# atmega128rf.net
KiCad netlist of a schematic drawn in Altium Designer
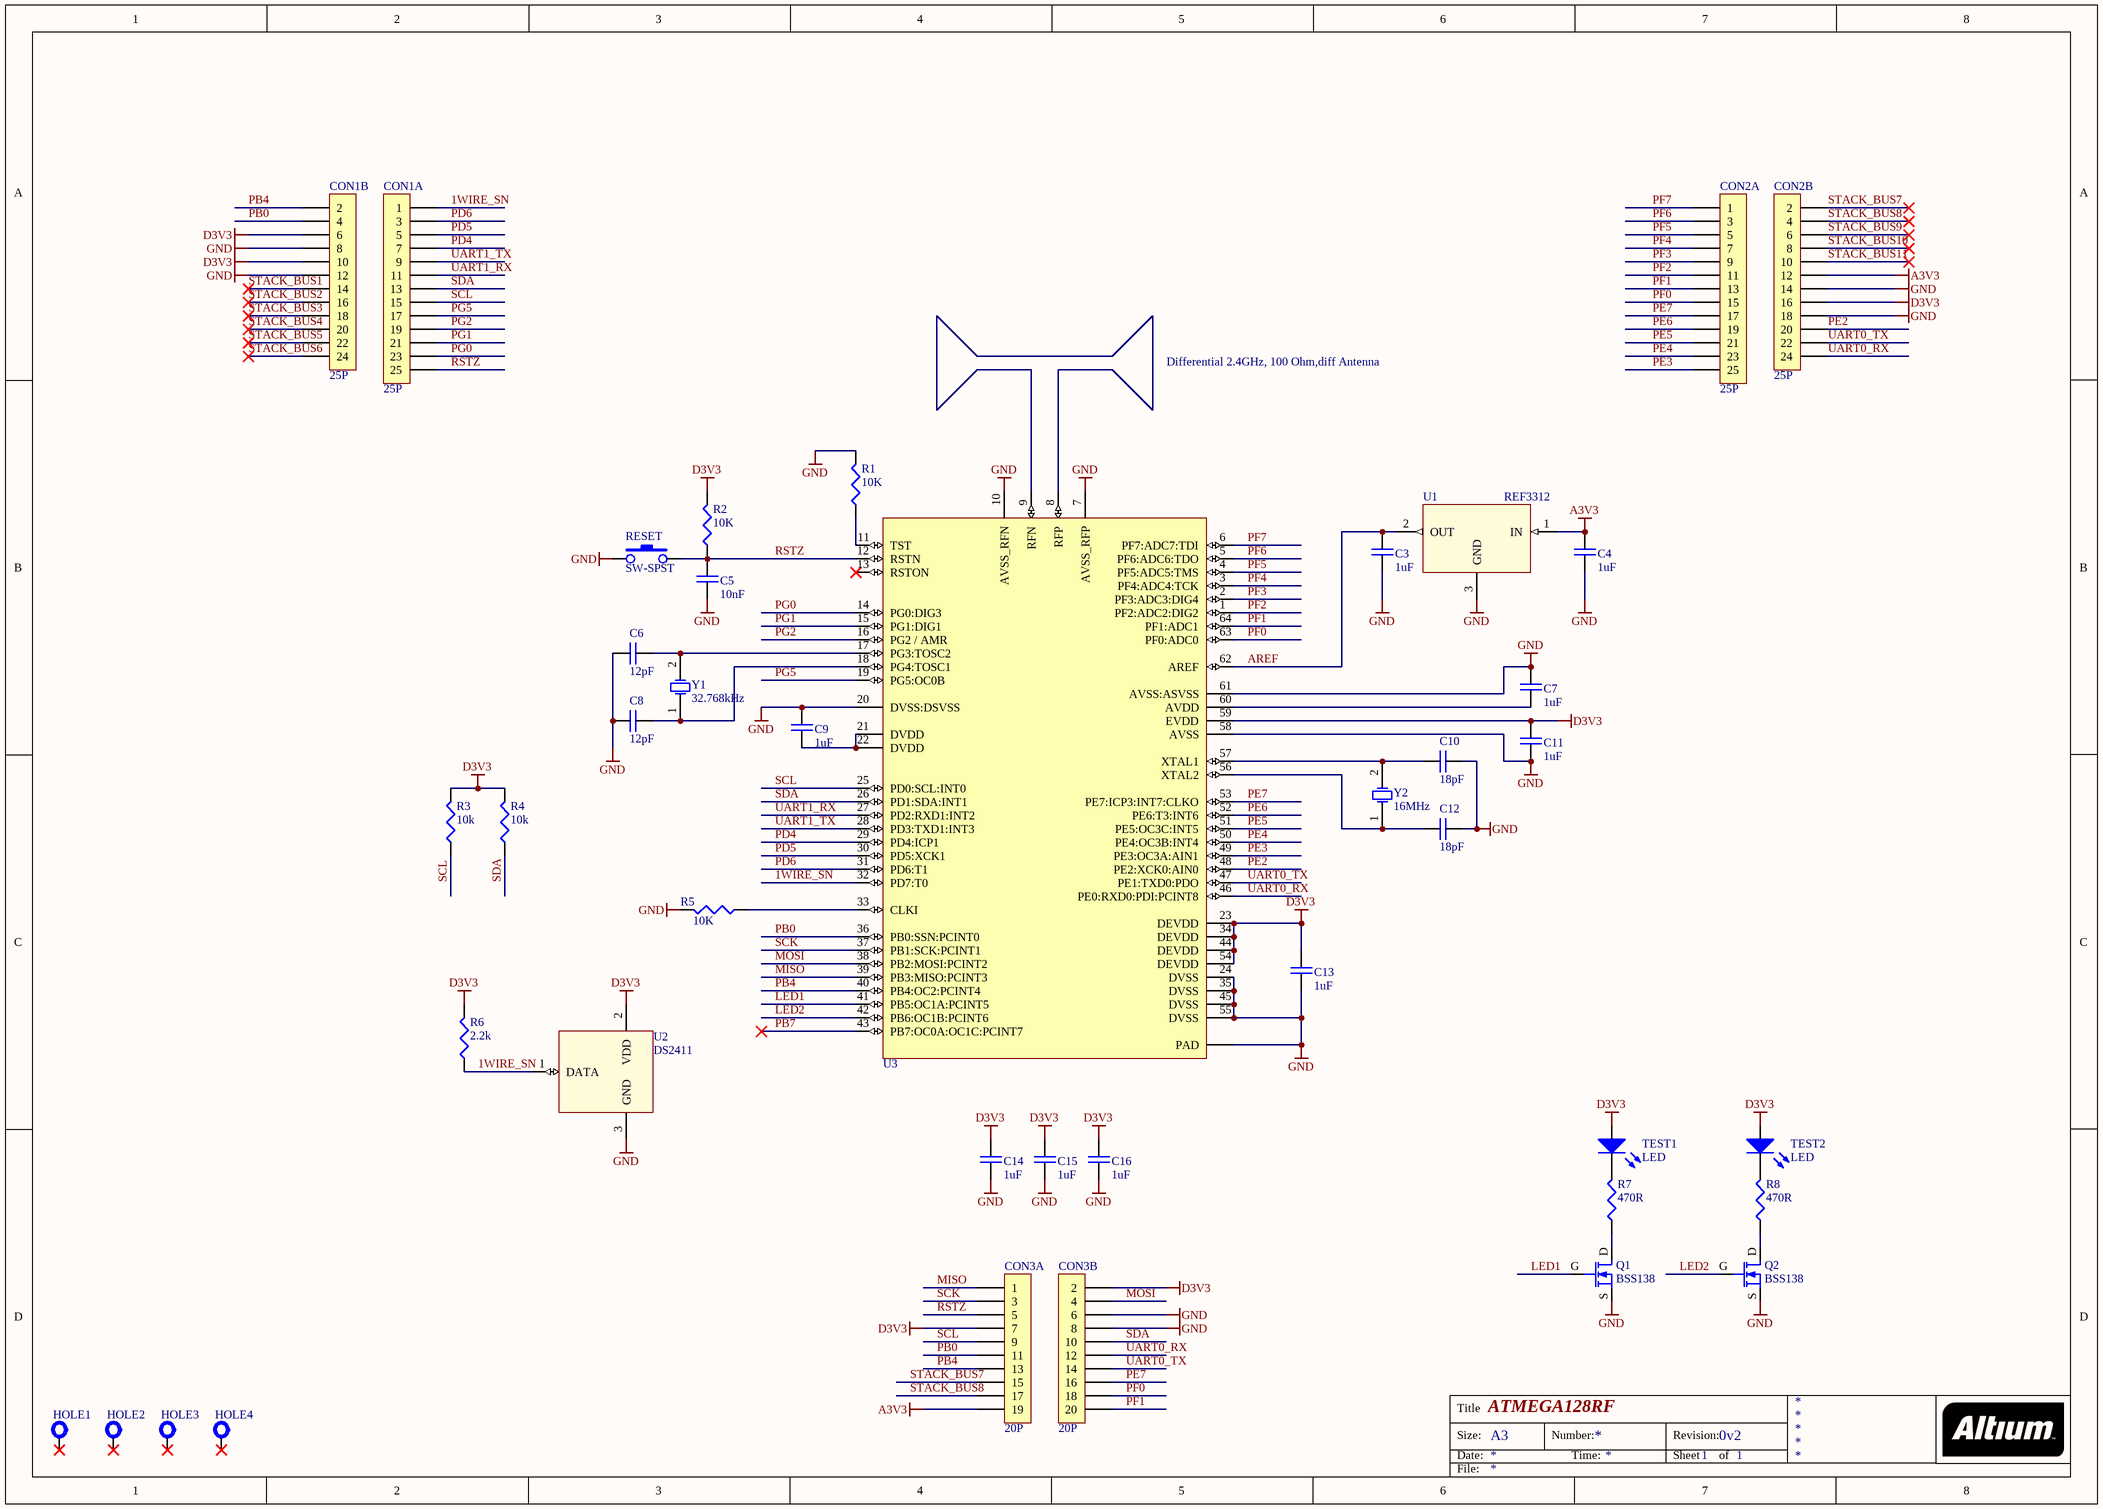
[diagram p0: atmega128rf.SchDoc]

(export (version "E")
  (design (tool "Eeschema 10.0.6"))
  (components
    (comp (ref "C3")
      (value "1uF")
      (footprint "0603")
      (description "Capacitor")
      (fields (field (name "OWNER") "Nuno Brum"))
      (libsource (lib "Alcetronics_Devices") (part "CAP"))
    )
    (comp (ref "C4")
      (value "1uF")
      (footprint "0603")
      (description "Capacitor")
      (fields (field (name "OWNER") "Nuno Brum"))
      (libsource (lib "Alcetronics_Devices") (part "CAP"))
    )
    (comp (ref "C5")
      (value "10nF")
      (footprint "0603")
      (description "Capacitor")
      (fields (field (name "OWNER") "Nuno Brum"))
      (libsource (lib "Alcetronics_Devices") (part "CAP"))
    )
    (comp (ref "C6")
      (value "12pF")
      (footprint "0603")
      (description "Capacitor")
      (fields (field (name "OWNER") "Nuno Brum"))
      (libsource (lib "Alcetronics_Devices") (part "CAP"))
    )
    (comp (ref "C7")
      (value "1uF")
      (footprint "0603")
      (description "Capacitor")
      (fields (field (name "OWNER") "Nuno Brum"))
      (libsource (lib "Alcetronics_Devices") (part "CAP"))
    )
    (comp (ref "C8")
      (value "12pF")
      (footprint "0603")
      (description "Capacitor")
      (fields (field (name "OWNER") "Nuno Brum"))
      (libsource (lib "Alcetronics_Devices") (part "CAP"))
    )
    (comp (ref "C9")
      (value "1uF")
      (footprint "0603")
      (description "Capacitor")
      (fields (field (name "OWNER") "Nuno Brum"))
      (libsource (lib "Alcetronics_Devices") (part "CAP"))
    )
    (comp (ref "C10")
      (value "18pF")
      (footprint "0603")
      (description "Capacitor")
      (fields (field (name "OWNER") "Nuno Brum"))
      (libsource (lib "Alcetronics_Devices") (part "CAP"))
    )
    (comp (ref "C11")
      (value "1uF")
      (footprint "0603")
      (description "Capacitor")
      (fields (field (name "OWNER") "Nuno Brum"))
      (libsource (lib "Alcetronics_Devices") (part "CAP"))
    )
    (comp (ref "C12")
      (value "18pF")
      (footprint "0603")
      (description "Capacitor")
      (fields (field (name "OWNER") "Nuno Brum"))
      (libsource (lib "Alcetronics_Devices") (part "CAP"))
    )
    (comp (ref "C13")
      (value "1uF")
      (footprint "0603")
      (description "Capacitor")
      (fields (field (name "OWNER") "Nuno Brum"))
      (libsource (lib "Alcetronics_Devices") (part "CAP"))
    )
    (comp (ref "C14")
      (value "1uF")
      (footprint "0603")
      (description "Capacitor")
      (fields (field (name "OWNER") "Nuno Brum"))
      (libsource (lib "Alcetronics_Devices") (part "CAP"))
    )
    (comp (ref "C15")
      (value "1uF")
      (footprint "0603")
      (description "Capacitor")
      (fields (field (name "OWNER") "Nuno Brum"))
      (libsource (lib "Alcetronics_Devices") (part "CAP"))
    )
    (comp (ref "C16")
      (value "1uF")
      (footprint "0603")
      (description "Capacitor")
      (fields (field (name "OWNER") "Nuno Brum"))
      (libsource (lib "Alcetronics_Devices") (part "CAP"))
    )
    (comp (ref "CON1")
      (value "25P")
      (footprint "DF9-25-STACK")
      (description "Connector 25 Pins")
      (fields (field (name "OWNER") "Ricardo Rodrigues"))
      (libsource (lib "Alcetronics_EM") (part "CON25"))
    )
    (comp (ref "CON2")
      (value "25P")
      (footprint "DF9-25-STACK")
      (description "Connector 25 Pins")
      (fields (field (name "OWNER") "Ricardo Rodrigues"))
      (libsource (lib "") (part "CON25_1"))
    )
    (comp (ref "CON3")
      (value "20P")
      (footprint "IDC-20-EDGE")
      (description "Connector 20 Pins")
      (fields (field (name "OWNER") "Nuno Brum"))
      (libsource (lib "Alcetronics_EM") (part "CON20"))
    )
    (comp (ref "HOLE1")
      (value "HOLE")
      (footprint "NPTH-3MM")
      (description "PCB Fixation Hole M3")
      (fields (field (name "OWNER") "Nuno Brum"))
      (libsource (lib "Alcetronics_EM") (part "PCB HOLE"))
    )
    (comp (ref "HOLE2")
      (value "HOLE")
      (footprint "NPTH-3MM")
      (description "PCB Fixation Hole M3")
      (fields (field (name "OWNER") "Nuno Brum"))
      (libsource (lib "Alcetronics_EM") (part "PCB HOLE"))
    )
    (comp (ref "HOLE3")
      (value "HOLE")
      (footprint "NPTH-3MM")
      (description "PCB Fixation Hole M3")
      (fields (field (name "OWNER") "Nuno Brum"))
      (libsource (lib "Alcetronics_EM") (part "PCB HOLE"))
    )
    (comp (ref "HOLE4")
      (value "HOLE")
      (footprint "NPTH-3MM")
      (description "PCB Fixation Hole M3")
      (fields (field (name "OWNER") "Nuno Brum"))
      (libsource (lib "Alcetronics_EM") (part "PCB HOLE"))
    )
    (comp (ref "Q1")
      (value "BSS138")
      (footprint "SOT-23@GSD")
      (description "N-Channel Logic Level Enhancement Mode Field Effect Transistor")
      (fields (field (name "OWNER") "Nuno Brum"))
      (libsource (lib "Alcetronics_Devices") (part "MOSFET-N"))
    )
    (comp (ref "Q2")
      (value "BSS138")
      (footprint "SOT-23@GSD")
      (description "N-Channel Logic Level Enhancement Mode Field Effect Transistor")
      (fields (field (name "OWNER") "Nuno Brum"))
      (libsource (lib "Alcetronics_Devices") (part "MOSFET-N"))
    )
    (comp (ref "R1")
      (value "10K")
      (footprint "0603")
      (description "Resistor")
      (fields (field (name "OWNER") "Nuno Brum"))
      (libsource (lib "Alcetronics_Devices") (part "RES"))
    )
    (comp (ref "R2")
      (value "10K")
      (footprint "0603")
      (description "Resistor")
      (fields (field (name "OWNER") "Nuno Brum"))
      (libsource (lib "Alcetronics_Devices") (part "RES"))
    )
    (comp (ref "R3")
      (value "10k")
      (footprint "0603")
      (description "Resistor")
      (fields (field (name "OWNER") "Nuno Brum"))
      (libsource (lib "Alcetronics_Devices") (part "RES"))
    )
    (comp (ref "R4")
      (value "10k")
      (footprint "0603")
      (description "Resistor")
      (fields (field (name "OWNER") "Nuno Brum"))
      (libsource (lib "Alcetronics_Devices") (part "RES"))
    )
    (comp (ref "R5")
      (value "10K")
      (footprint "0603")
      (description "Resistor")
      (fields (field (name "OWNER") "Nuno Brum"))
      (libsource (lib "Alcetronics_Devices") (part "RES"))
    )
    (comp (ref "R6")
      (value "2.2k")
      (footprint "0603")
      (description "Resistor")
      (fields (field (name "OWNER") "Nuno Brum"))
      (libsource (lib "Alcetronics_Devices") (part "RES"))
    )
    (comp (ref "R7")
      (value "470R")
      (footprint "0603")
      (description "Resistor")
      (fields (field (name "OWNER") "Nuno Brum"))
      (libsource (lib "Alcetronics_Devices") (part "RES"))
    )
    (comp (ref "R8")
      (value "470R")
      (footprint "0603")
      (description "Resistor")
      (fields (field (name "OWNER") "Nuno Brum"))
      (libsource (lib "Alcetronics_Devices") (part "RES"))
    )
    (comp (ref "RESET")
      (value "SW-SPST")
      (footprint "MICROSWITCH-RA")
      (description "Switch Push Button")
      (fields (field (name "OWNER") "Ricardo Rodrigues"))
      (libsource (lib "Alcetronics_EM") (part "SW-SPST"))
    )
    (comp (ref "TEST1")
      (value "LED")
      (footprint "0805@DIODE")
      (description "Light emitting diode")
      (fields (field (name "OWNER") "Nuno Brum"))
      (libsource (lib "Alcetronics_Devices") (part "LED"))
    )
    (comp (ref "TEST2")
      (value "LED")
      (footprint "0805@DIODE")
      (description "Light emitting diode")
      (fields (field (name "OWNER") "Nuno Brum"))
      (libsource (lib "Alcetronics_Devices") (part "LED"))
    )
    (comp (ref "U1")
      (value "REF3312")
      (footprint "SOT-23")
      (description "Voltage Reference 1.25V, 30ppm/degC, 5mA")
      (libsource (lib "Alcetronics_IC") (part "REF3312"))
    )
    (comp (ref "U2")
      (value "DS2411")
      (footprint "SOT-23")
      (description "Silicon Serial Number")
      (libsource (lib "Alcetronics_IC") (part "DS2411"))
    )
    (comp (ref "U3")
      (value "ATmega128RFA1")
      (footprint "QFN-64@EP")
      (description "802.15.4 compliant AVR transceiver")
      (fields (field (name "VERIFIED BY") "vlarsen"))
      (libsource (lib "Alcetronics_IC") (part "ATmega128RFA1"))
    )
    (comp (ref "Y1")
      (value "32.768kHz")
      (footprint "XTAL-SMD-4.9x1.8")
      (description "Crystal Oscillator")
      (fields (field (name "PUBLISHER") "Altium Limited"))
      (libsource (lib "Alcetronics_Devices") (part "Crystal Oscillator"))
    )
    (comp (ref "Y2")
      (value "16MHz")
      (footprint "HC49/4HSMX")
      (description "Crystal Oscillator")
      (fields (field (name "PUBLISHER") "Altium Limited"))
      (libsource (lib "Alcetronics_Devices") (part "Crystal Oscillator"))
    )
  )
  (nets
    (net (code "1") (name "/1WIRE_SN") (class "Default")
      (node (ref "CON1") (pin "1") (pinfunction "1_1") (pintype "passive"))
      (node (ref "R6") (pin "1") (pinfunction "1_1") (pintype "passive"))
      (node (ref "U2") (pin "1") (pinfunction "DATA_1") (pintype "bidirectional"))
      (node (ref "U3") (pin "32") (pinfunction "PD7:T0_32") (pintype "bidirectional"))
    )
    (net (code "2") (name "/AREF") (class "Default")
      (node (ref "C3") (pin "1") (pinfunction "1_1") (pintype "passive"))
      (node (ref "U1") (pin "2") (pinfunction "OUT_2") (pintype "output"))
      (node (ref "U3") (pin "62") (pinfunction "AREF_62") (pintype "bidirectional"))
    )
    (net (code "3") (name "/LED1") (class "Default")
      (node (ref "Q1") (pin "G") (pinfunction "G_G") (pintype "passive"))
      (node (ref "U3") (pin "41") (pinfunction "PB5:OC1A:PCINT5_41") (pintype "bidirectional"))
    )
    (net (code "4") (name "/LED2") (class "Default")
      (node (ref "Q2") (pin "G") (pinfunction "G_G") (pintype "passive"))
      (node (ref "U3") (pin "42") (pinfunction "PB6:OC1B:PCINT6_42") (pintype "bidirectional"))
    )
    (net (code "5") (name "/MISO") (class "Default")
      (node (ref "CON3") (pin "1") (pinfunction "1_1") (pintype "passive"))
      (node (ref "U3") (pin "39") (pinfunction "PB3:MISO:PCINT3_39") (pintype "bidirectional"))
    )
    (net (code "6") (name "/MOSI") (class "Default")
      (node (ref "CON3") (pin "4") (pinfunction "4_4") (pintype "passive"))
      (node (ref "U3") (pin "38") (pinfunction "PB2:MOSI:PCINT2_38") (pintype "bidirectional"))
    )
    (net (code "7") (name "/PB0") (class "Default")
      (node (ref "CON1") (pin "4") (pinfunction "4_4") (pintype "passive"))
      (node (ref "CON3") (pin "11") (pinfunction "11_11") (pintype "passive"))
      (node (ref "U3") (pin "36") (pinfunction "PB0:SSN:PCINT0_36") (pintype "bidirectional"))
    )
    (net (code "8") (name "/PB4") (class "Default")
      (node (ref "CON1") (pin "2") (pinfunction "2_2") (pintype "passive"))
      (node (ref "CON3") (pin "13") (pinfunction "13_13") (pintype "passive"))
      (node (ref "U3") (pin "40") (pinfunction "PB4:OC2:PCINT4_40") (pintype "bidirectional"))
    )
    (net (code "9") (name "/PB7") (class "Default")
      (node (ref "U3") (pin "43") (pinfunction "PB7:OC0A:OC1C:PCINT7_43") (pintype "bidirectional+no_connect"))
    )
    (net (code "10") (name "/PD4") (class "Default")
      (node (ref "CON1") (pin "7") (pinfunction "7_7") (pintype "passive"))
      (node (ref "U3") (pin "29") (pinfunction "PD4:ICP1_29") (pintype "bidirectional"))
    )
    (net (code "11") (name "/PD5") (class "Default")
      (node (ref "CON1") (pin "5") (pinfunction "5_5") (pintype "passive"))
      (node (ref "U3") (pin "30") (pinfunction "PD5:XCK1_30") (pintype "bidirectional"))
    )
    (net (code "12") (name "/PD6") (class "Default")
      (node (ref "CON1") (pin "3") (pinfunction "3_3") (pintype "passive"))
      (node (ref "U3") (pin "31") (pinfunction "PD6:T1_31") (pintype "bidirectional"))
    )
    (net (code "13") (name "/PE2") (class "Default")
      (node (ref "CON2") (pin "20") (pinfunction "20_20") (pintype "passive"))
      (node (ref "U3") (pin "48") (pinfunction "PE2:XCK0:AIN0_48") (pintype "bidirectional"))
    )
    (net (code "14") (name "/PE3") (class "Default")
      (node (ref "CON2") (pin "25") (pinfunction "25_25") (pintype "passive"))
      (node (ref "U3") (pin "49") (pinfunction "PE3:OC3A:AIN1_49") (pintype "bidirectional"))
    )
    (net (code "15") (name "/PE4") (class "Default")
      (node (ref "CON2") (pin "23") (pinfunction "23_23") (pintype "passive"))
      (node (ref "U3") (pin "50") (pinfunction "PE4:OC3B:INT4_50") (pintype "bidirectional"))
    )
    (net (code "16") (name "/PE5") (class "Default")
      (node (ref "CON2") (pin "21") (pinfunction "21_21") (pintype "passive"))
      (node (ref "U3") (pin "51") (pinfunction "PE5:OC3C:INT5_51") (pintype "bidirectional"))
    )
    (net (code "17") (name "/PE6") (class "Default")
      (node (ref "CON2") (pin "19") (pinfunction "19_19") (pintype "passive"))
      (node (ref "U3") (pin "52") (pinfunction "PE6:T3:INT6_52") (pintype "bidirectional"))
    )
    (net (code "18") (name "/PE7") (class "Default")
      (node (ref "CON2") (pin "17") (pinfunction "17_17") (pintype "passive"))
      (node (ref "CON3") (pin "16") (pinfunction "16_16") (pintype "passive"))
      (node (ref "U3") (pin "53") (pinfunction "PE7:ICP3:INT7:CLKO_53") (pintype "bidirectional"))
    )
    (net (code "19") (name "/PF0") (class "Default")
      (node (ref "CON2") (pin "15") (pinfunction "15_15") (pintype "passive"))
      (node (ref "CON3") (pin "18") (pinfunction "18_18") (pintype "passive"))
      (node (ref "U3") (pin "63") (pinfunction "PF0:ADC0_63") (pintype "bidirectional"))
    )
    (net (code "20") (name "/PF1") (class "Default")
      (node (ref "CON2") (pin "13") (pinfunction "13_13") (pintype "passive"))
      (node (ref "CON3") (pin "20") (pinfunction "20_20") (pintype "passive"))
      (node (ref "U3") (pin "64") (pinfunction "PF1:ADC1_64") (pintype "bidirectional"))
    )
    (net (code "21") (name "/PF2") (class "Default")
      (node (ref "CON2") (pin "11") (pinfunction "11_11") (pintype "passive"))
      (node (ref "U3") (pin "1") (pinfunction "PF2:ADC2:DIG2_1") (pintype "bidirectional"))
    )
    (net (code "22") (name "/PF3") (class "Default")
      (node (ref "CON2") (pin "9") (pinfunction "9_9") (pintype "passive"))
      (node (ref "U3") (pin "2") (pinfunction "PF3:ADC3:DIG4_2") (pintype "bidirectional"))
    )
    (net (code "23") (name "/PF4") (class "Default")
      (node (ref "CON2") (pin "7") (pinfunction "7_7") (pintype "passive"))
      (node (ref "U3") (pin "3") (pinfunction "PF4:ADC4:TCK_3") (pintype "bidirectional"))
    )
    (net (code "24") (name "/PF5") (class "Default")
      (node (ref "CON2") (pin "5") (pinfunction "5_5") (pintype "passive"))
      (node (ref "U3") (pin "4") (pinfunction "PF5:ADC5:TMS_4") (pintype "bidirectional"))
    )
    (net (code "25") (name "/PF6") (class "Default")
      (node (ref "CON2") (pin "3") (pinfunction "3_3") (pintype "passive"))
      (node (ref "U3") (pin "5") (pinfunction "PF6:ADC6:TDO_5") (pintype "bidirectional"))
    )
    (net (code "26") (name "/PF7") (class "Default")
      (node (ref "CON2") (pin "1") (pinfunction "1_1") (pintype "passive"))
      (node (ref "U3") (pin "6") (pinfunction "PF7:ADC7:TDI_6") (pintype "bidirectional"))
    )
    (net (code "27") (name "/PG0") (class "Default")
      (node (ref "CON1") (pin "23") (pinfunction "23_23") (pintype "passive"))
      (node (ref "U3") (pin "14") (pinfunction "PG0:DIG3_14") (pintype "bidirectional"))
    )
    (net (code "28") (name "/PG1") (class "Default")
      (node (ref "CON1") (pin "21") (pinfunction "21_21") (pintype "passive"))
      (node (ref "U3") (pin "15") (pinfunction "PG1:DIG1_15") (pintype "bidirectional"))
    )
    (net (code "29") (name "/PG2") (class "Default")
      (node (ref "CON1") (pin "19") (pinfunction "19_19") (pintype "passive"))
      (node (ref "U3") (pin "16") (pinfunction "PG2_/_AMR_16") (pintype "bidirectional"))
    )
    (net (code "30") (name "/PG5") (class "Default")
      (node (ref "CON1") (pin "17") (pinfunction "17_17") (pintype "passive"))
      (node (ref "U3") (pin "19") (pinfunction "PG5:OC0B_19") (pintype "bidirectional"))
    )
    (net (code "31") (name "/RSTZ") (class "Default")
      (node (ref "C5") (pin "1") (pinfunction "1_1") (pintype "passive"))
      (node (ref "CON1") (pin "25") (pinfunction "25_25") (pintype "passive"))
      (node (ref "CON3") (pin "5") (pinfunction "5_5") (pintype "passive"))
      (node (ref "R2") (pin "1") (pinfunction "1_1") (pintype "passive"))
      (node (ref "RESET") (pin "2") (pinfunction "2_2") (pintype "passive"))
      (node (ref "U3") (pin "12") (pinfunction "RSTN_12") (pintype "bidirectional"))
    )
    (net (code "32") (name "/SCK") (class "Default")
      (node (ref "CON3") (pin "3") (pinfunction "3_3") (pintype "passive"))
      (node (ref "U3") (pin "37") (pinfunction "PB1:SCK:PCINT1_37") (pintype "bidirectional"))
    )
    (net (code "33") (name "/SCL") (class "Default")
      (node (ref "CON1") (pin "15") (pinfunction "15_15") (pintype "passive"))
      (node (ref "CON3") (pin "9") (pinfunction "9_9") (pintype "passive"))
      (node (ref "R3") (pin "1") (pinfunction "1_1") (pintype "passive"))
      (node (ref "U3") (pin "25") (pinfunction "PD0:SCL:INT0_25") (pintype "bidirectional"))
    )
    (net (code "34") (name "/SDA") (class "Default")
      (node (ref "CON1") (pin "13") (pinfunction "13_13") (pintype "passive"))
      (node (ref "CON3") (pin "10") (pinfunction "10_10") (pintype "passive"))
      (node (ref "R4") (pin "1") (pinfunction "1_1") (pintype "passive"))
      (node (ref "U3") (pin "26") (pinfunction "PD1:SDA:INT1_26") (pintype "bidirectional"))
    )
    (net (code "35") (name "/STACK_BUS1") (class "Default")
      (node (ref "CON1") (pin "14") (pinfunction "14_14") (pintype "passive+no_connect"))
    )
    (net (code "36") (name "/STACK_BUS2") (class "Default")
      (node (ref "CON1") (pin "16") (pinfunction "16_16") (pintype "passive+no_connect"))
    )
    (net (code "37") (name "/STACK_BUS3") (class "Default")
      (node (ref "CON1") (pin "18") (pinfunction "18_18") (pintype "passive+no_connect"))
    )
    (net (code "38") (name "/STACK_BUS4") (class "Default")
      (node (ref "CON1") (pin "20") (pinfunction "20_20") (pintype "passive+no_connect"))
    )
    (net (code "39") (name "/STACK_BUS5") (class "Default")
      (node (ref "CON1") (pin "22") (pinfunction "22_22") (pintype "passive+no_connect"))
    )
    (net (code "40") (name "/STACK_BUS6") (class "Default")
      (node (ref "CON1") (pin "24") (pinfunction "24_24") (pintype "passive+no_connect"))
    )
    (net (code "41") (name "/STACK_BUS7") (class "Default")
      (node (ref "CON2") (pin "2") (pinfunction "2_2") (pintype "passive"))
      (node (ref "CON3") (pin "15") (pinfunction "15_15") (pintype "passive"))
    )
    (net (code "42") (name "/STACK_BUS8") (class "Default")
      (node (ref "CON2") (pin "4") (pinfunction "4_4") (pintype "passive"))
      (node (ref "CON3") (pin "17") (pinfunction "17_17") (pintype "passive"))
    )
    (net (code "43") (name "/STACK_BUS9") (class "Default")
      (node (ref "CON2") (pin "6") (pinfunction "6_6") (pintype "passive+no_connect"))
    )
    (net (code "44") (name "/STACK_BUS10") (class "Default")
      (node (ref "CON2") (pin "8") (pinfunction "8_8") (pintype "passive+no_connect"))
    )
    (net (code "45") (name "/STACK_BUS11") (class "Default")
      (node (ref "CON2") (pin "10") (pinfunction "10_10") (pintype "passive+no_connect"))
    )
    (net (code "46") (name "/UART0_RX") (class "Default")
      (node (ref "CON2") (pin "24") (pinfunction "24_24") (pintype "passive"))
      (node (ref "CON3") (pin "12") (pinfunction "12_12") (pintype "passive"))
      (node (ref "U3") (pin "46") (pinfunction "PE0:RXD0:PDI:PCINT8_46") (pintype "bidirectional"))
    )
    (net (code "47") (name "/UART0_TX") (class "Default")
      (node (ref "CON2") (pin "22") (pinfunction "22_22") (pintype "passive"))
      (node (ref "CON3") (pin "14") (pinfunction "14_14") (pintype "passive"))
      (node (ref "U3") (pin "47") (pinfunction "PE1:TXD0:PDO_47") (pintype "bidirectional"))
    )
    (net (code "48") (name "/UART1_RX") (class "Default")
      (node (ref "CON1") (pin "11") (pinfunction "11_11") (pintype "passive"))
      (node (ref "U3") (pin "27") (pinfunction "PD2:RXD1:INT2_27") (pintype "bidirectional"))
    )
    (net (code "49") (name "/UART1_TX") (class "Default")
      (node (ref "CON1") (pin "9") (pinfunction "9_9") (pintype "passive"))
      (node (ref "U3") (pin "28") (pinfunction "PD3:TXD1:INT3_28") (pintype "bidirectional"))
    )
    (net (code "50") (name "A3V3") (class "Default")
      (node (ref "C4") (pin "1") (pinfunction "1_1") (pintype "passive"))
      (node (ref "CON2") (pin "12") (pinfunction "12_12") (pintype "passive"))
      (node (ref "CON3") (pin "19") (pinfunction "19_19") (pintype "passive"))
      (node (ref "U1") (pin "1") (pinfunction "IN_1") (pintype "input"))
    )
    (net (code "51") (name "D3V3") (class "Default")
      (node (ref "C11") (pin "2") (pinfunction "2_2") (pintype "passive"))
      (node (ref "C13") (pin "2") (pinfunction "2_2") (pintype "passive"))
      (node (ref "C14") (pin "2") (pinfunction "2_2") (pintype "passive"))
      (node (ref "C15") (pin "2") (pinfunction "2_2") (pintype "passive"))
      (node (ref "C16") (pin "2") (pinfunction "2_2") (pintype "passive"))
      (node (ref "CON1") (pin "10") (pinfunction "10_10") (pintype "passive"))
      (node (ref "CON1") (pin "6") (pinfunction "6_6") (pintype "passive"))
      (node (ref "CON2") (pin "16") (pinfunction "16_16") (pintype "passive"))
      (node (ref "CON3") (pin "2") (pinfunction "2_2") (pintype "passive"))
      (node (ref "CON3") (pin "7") (pinfunction "7_7") (pintype "passive"))
      (node (ref "R2") (pin "2") (pinfunction "2_2") (pintype "passive"))
      (node (ref "R3") (pin "2") (pinfunction "2_2") (pintype "passive"))
      (node (ref "R4") (pin "2") (pinfunction "2_2") (pintype "passive"))
      (node (ref "R6") (pin "2") (pinfunction "2_2") (pintype "passive"))
      (node (ref "TEST1") (pin "A") (pinfunction "A_A") (pintype "passive"))
      (node (ref "TEST2") (pin "A") (pinfunction "A_A") (pintype "passive"))
      (node (ref "U2") (pin "2") (pinfunction "VDD_2") (pintype "power_in"))
      (node (ref "U3") (pin "23") (pinfunction "DEVDD_23") (pintype "power_in"))
      (node (ref "U3") (pin "34") (pinfunction "DEVDD_34") (pintype "power_in"))
      (node (ref "U3") (pin "44") (pinfunction "DEVDD_44") (pintype "power_in"))
      (node (ref "U3") (pin "54") (pinfunction "DEVDD_54") (pintype "power_in"))
      (node (ref "U3") (pin "59") (pinfunction "EVDD_59") (pintype "power_in"))
    )
    (net (code "52") (name "GND") (class "Default")
      (node (ref "C10") (pin "2") (pinfunction "2_2") (pintype "passive"))
      (node (ref "C11") (pin "1") (pinfunction "1_1") (pintype "passive"))
      (node (ref "C12") (pin "2") (pinfunction "2_2") (pintype "passive"))
      (node (ref "C13") (pin "1") (pinfunction "1_1") (pintype "passive"))
      (node (ref "C14") (pin "1") (pinfunction "1_1") (pintype "passive"))
      (node (ref "C15") (pin "1") (pinfunction "1_1") (pintype "passive"))
      (node (ref "C16") (pin "1") (pinfunction "1_1") (pintype "passive"))
      (node (ref "C3") (pin "2") (pinfunction "2_2") (pintype "passive"))
      (node (ref "C4") (pin "2") (pinfunction "2_2") (pintype "passive"))
      (node (ref "C5") (pin "2") (pinfunction "2_2") (pintype "passive"))
      (node (ref "C6") (pin "1") (pinfunction "1_1") (pintype "passive"))
      (node (ref "C7") (pin "2") (pinfunction "2_2") (pintype "passive"))
      (node (ref "C8") (pin "1") (pinfunction "1_1") (pintype "passive"))
      (node (ref "C9") (pin "2") (pinfunction "2_2") (pintype "passive"))
      (node (ref "CON1") (pin "12") (pinfunction "12_12") (pintype "passive"))
      (node (ref "CON1") (pin "8") (pinfunction "8_8") (pintype "passive"))
      (node (ref "CON2") (pin "14") (pinfunction "14_14") (pintype "passive"))
      (node (ref "CON2") (pin "18") (pinfunction "18_18") (pintype "passive"))
      (node (ref "CON3") (pin "6") (pinfunction "6_6") (pintype "passive"))
      (node (ref "CON3") (pin "8") (pinfunction "8_8") (pintype "passive"))
      (node (ref "Q1") (pin "S") (pinfunction "S_S") (pintype "passive"))
      (node (ref "Q2") (pin "S") (pinfunction "S_S") (pintype "passive"))
      (node (ref "R1") (pin "2") (pinfunction "2_2") (pintype "passive"))
      (node (ref "R5") (pin "2") (pinfunction "2_2") (pintype "passive"))
      (node (ref "RESET") (pin "1") (pinfunction "1_1") (pintype "passive"))
      (node (ref "U1") (pin "3") (pinfunction "GND_3") (pintype "power_in"))
      (node (ref "U2") (pin "3") (pinfunction "GND_3") (pintype "power_in"))
      (node (ref "U3") (pin "10") (pinfunction "AVSS_RFN_10") (pintype "power_in"))
      (node (ref "U3") (pin "20") (pinfunction "DVSS:DSVSS_20") (pintype "power_in"))
      (node (ref "U3") (pin "24") (pinfunction "DVSS_24") (pintype "power_in"))
      (node (ref "U3") (pin "35") (pinfunction "DVSS_35") (pintype "power_in"))
      (node (ref "U3") (pin "45") (pinfunction "DVSS_45") (pintype "power_in"))
      (node (ref "U3") (pin "55") (pinfunction "DVSS_55") (pintype "power_in"))
      (node (ref "U3") (pin "58") (pinfunction "AVSS_58") (pintype "power_in"))
      (node (ref "U3") (pin "61") (pinfunction "AVSS:ASVSS_61") (pintype "power_in"))
      (node (ref "U3") (pin "7") (pinfunction "AVSS_RFP_7") (pintype "power_in"))
      (node (ref "U3") (pin "PAD") (pinfunction "PAD_PAD") (pintype "power_in"))
    )
    (net (code "53") (name "Net-(C9-Pad1)") (class "Default")
      (node (ref "C9") (pin "1") (pinfunction "1_1") (pintype "passive"))
      (node (ref "U3") (pin "21") (pinfunction "DVDD_21") (pintype "power_in"))
      (node (ref "U3") (pin "22") (pinfunction "DVDD_22") (pintype "power_in"))
    )
    (net (code "54") (name "Net-(Q1-PadD)") (class "Default")
      (node (ref "Q1") (pin "D") (pinfunction "D_D") (pintype "passive"))
      (node (ref "R7") (pin "1") (pinfunction "1_1") (pintype "passive"))
    )
    (net (code "55") (name "Net-(Q2-PadD)") (class "Default")
      (node (ref "Q2") (pin "D") (pinfunction "D_D") (pintype "passive"))
      (node (ref "R8") (pin "1") (pinfunction "1_1") (pintype "passive"))
    )
    (net (code "56") (name "Net-(R7-Pad2)") (class "Default")
      (node (ref "R7") (pin "2") (pinfunction "2_2") (pintype "passive"))
      (node (ref "TEST1") (pin "K") (pinfunction "K_K") (pintype "passive"))
    )
    (net (code "57") (name "Net-(R8-Pad2)") (class "Default")
      (node (ref "R8") (pin "2") (pinfunction "2_2") (pintype "passive"))
      (node (ref "TEST2") (pin "K") (pinfunction "K_K") (pintype "passive"))
    )
    (net (code "58") (name "Net-(U3-AVDD)") (class "Default")
      (node (ref "C7") (pin "1") (pinfunction "1_1") (pintype "passive"))
      (node (ref "U3") (pin "60") (pinfunction "AVDD_60") (pintype "power_in"))
    )
    (net (code "59") (name "Net-(U3-CLKI)") (class "Default")
      (node (ref "R5") (pin "1") (pinfunction "1_1") (pintype "passive"))
      (node (ref "U3") (pin "33") (pinfunction "CLKI_33") (pintype "bidirectional"))
    )
    (net (code "60") (name "Net-(U3-PG3:TOSC2)") (class "Default")
      (node (ref "C6") (pin "2") (pinfunction "2_2") (pintype "passive"))
      (node (ref "U3") (pin "17") (pinfunction "PG3:TOSC2_17") (pintype "bidirectional"))
      (node (ref "Y1") (pin "2") (pinfunction "OSC2_2") (pintype "passive"))
    )
    (net (code "61") (name "Net-(U3-PG4:TOSC1)") (class "Default")
      (node (ref "C8") (pin "2") (pinfunction "2_2") (pintype "passive"))
      (node (ref "U3") (pin "18") (pinfunction "PG4:TOSC1_18") (pintype "bidirectional"))
      (node (ref "Y1") (pin "1") (pinfunction "OSC1_1") (pintype "passive"))
    )
    (net (code "62") (name "Net-(U3-RFN)") (class "Default")
      (node (ref "U3") (pin "8") (pinfunction "RFP_8") (pintype "bidirectional"))
      (node (ref "U3") (pin "9") (pinfunction "RFN_9") (pintype "bidirectional"))
    )
    (net (code "63") (name "Net-(U3-TST)") (class "Default")
      (node (ref "R1") (pin "1") (pinfunction "1_1") (pintype "passive"))
      (node (ref "U3") (pin "11") (pinfunction "TST_11") (pintype "bidirectional"))
    )
    (net (code "64") (name "Net-(U3-XTAL1)") (class "Default")
      (node (ref "C10") (pin "1") (pinfunction "1_1") (pintype "passive"))
      (node (ref "U3") (pin "57") (pinfunction "XTAL1_57") (pintype "bidirectional"))
      (node (ref "Y2") (pin "2") (pinfunction "OSC2_2") (pintype "passive"))
    )
    (net (code "65") (name "Net-(U3-XTAL2)") (class "Default")
      (node (ref "C12") (pin "1") (pinfunction "1_1") (pintype "passive"))
      (node (ref "U3") (pin "56") (pinfunction "XTAL2_56") (pintype "bidirectional"))
      (node (ref "Y2") (pin "1") (pinfunction "OSC1_1") (pintype "passive"))
    )
    (net (code "66") (name "unconnected-(HOLE1-TP-Pad1)") (class "Default")
      (node (ref "HOLE1") (pin "1") (pinfunction "TP_1") (pintype "passive+no_connect"))
    )
    (net (code "67") (name "unconnected-(HOLE2-TP-Pad1)") (class "Default")
      (node (ref "HOLE2") (pin "1") (pinfunction "TP_1") (pintype "passive+no_connect"))
    )
    (net (code "68") (name "unconnected-(HOLE3-TP-Pad1)") (class "Default")
      (node (ref "HOLE3") (pin "1") (pinfunction "TP_1") (pintype "passive+no_connect"))
    )
    (net (code "69") (name "unconnected-(HOLE4-TP-Pad1)") (class "Default")
      (node (ref "HOLE4") (pin "1") (pinfunction "TP_1") (pintype "passive+no_connect"))
    )
    (net (code "70") (name "unconnected-(U3-RSTON-Pad13)") (class "Default")
      (node (ref "U3") (pin "13") (pinfunction "RSTON_13") (pintype "bidirectional+no_connect"))
    )
  )
)
